# smits-board.net
KiCad netlist of a schematic drawn in EAGLE
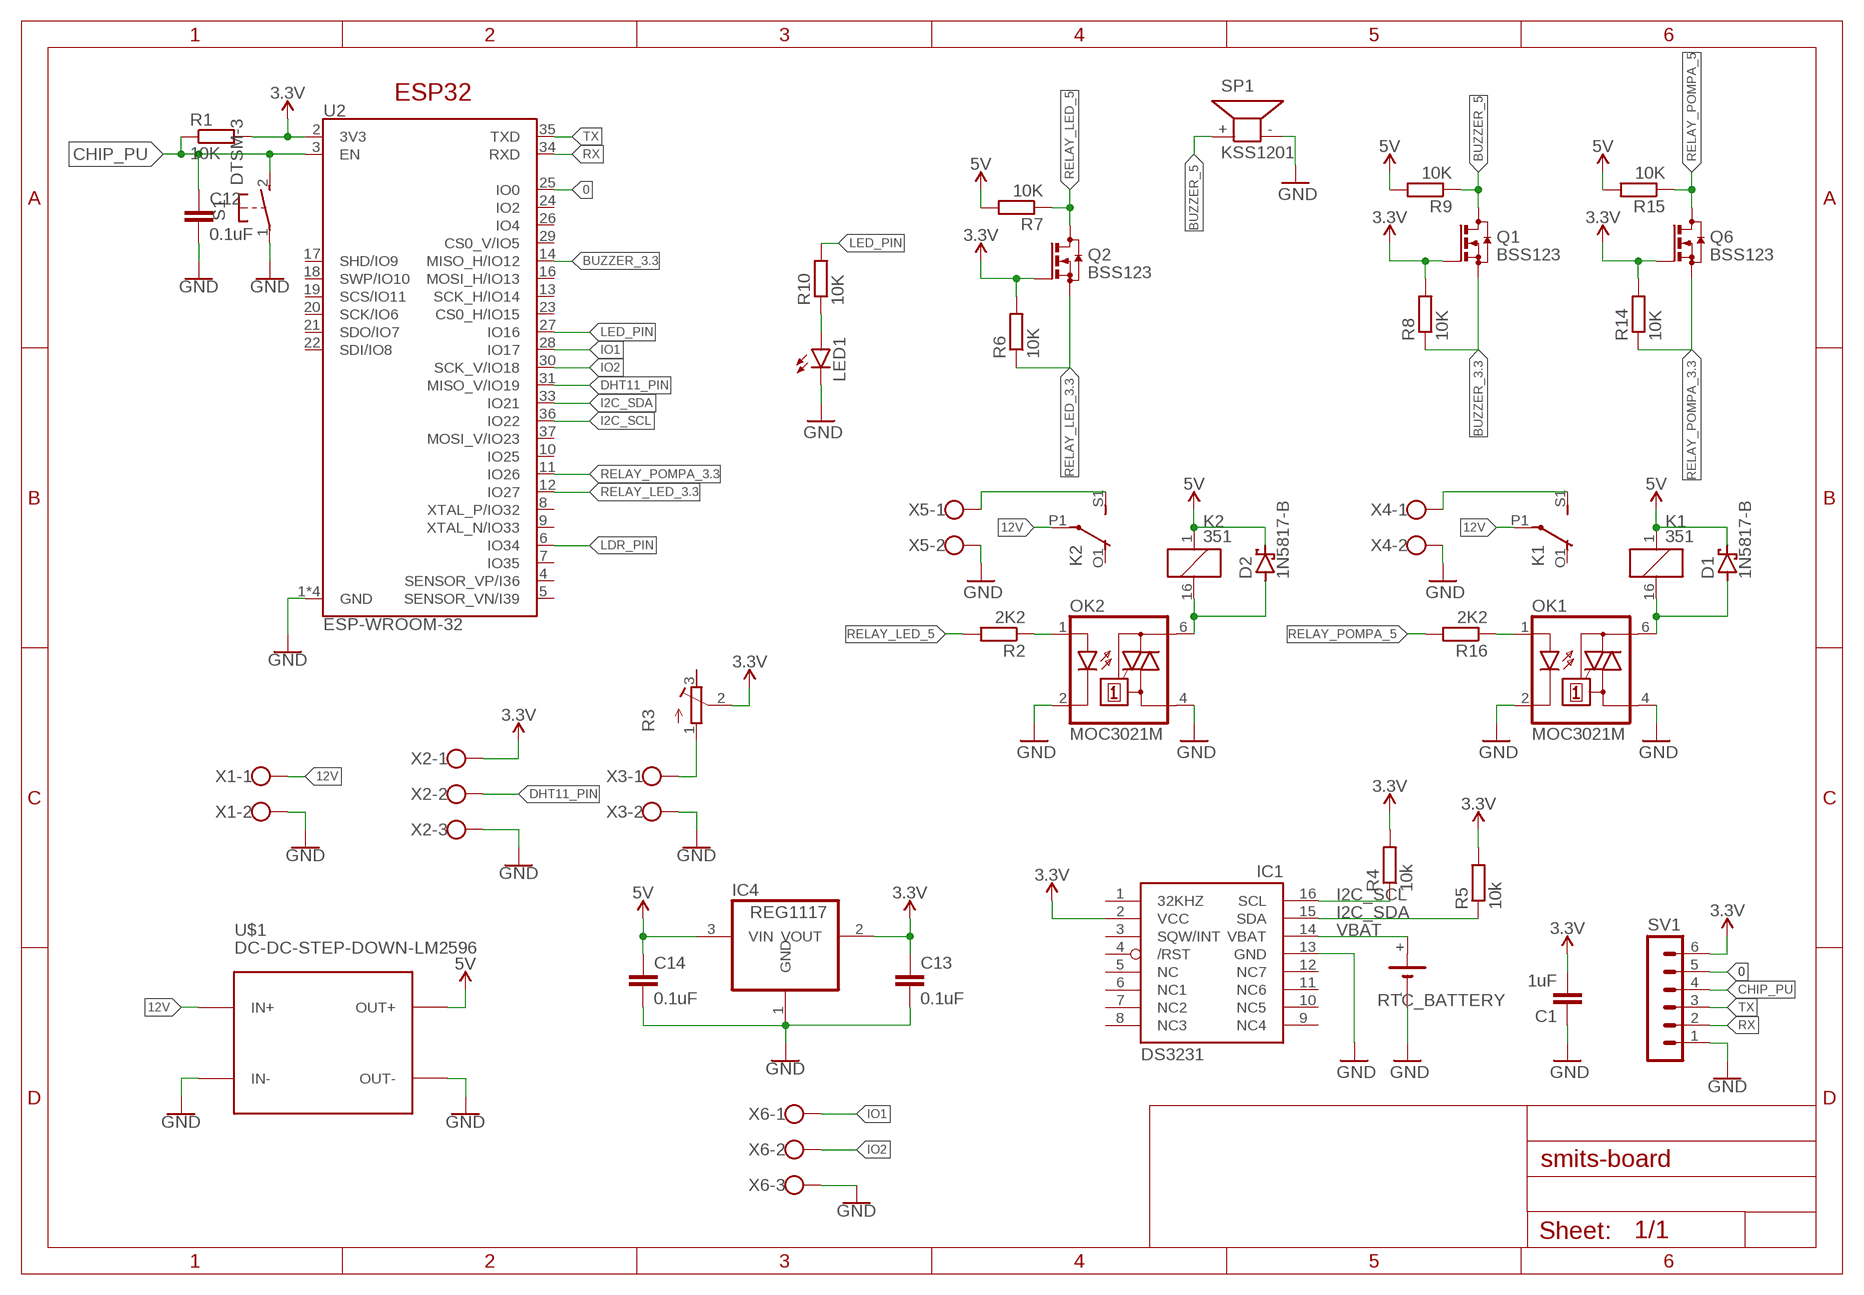
[diagram p0: schematic, sheet 1]

(export (version "E")
  (design (tool "Eeschema 10.0.6"))
  (components
    (comp (ref "C1")
      (value "1uF")
      (footprint "eagle-import:C0805")
      (libsource (lib "eagle-import") (part "C-EUC0805"))
    )
    (comp (ref "C12")
      (value "0.1uF")
      (footprint "eagle-import:C0805")
      (libsource (lib "eagle-import") (part "C-EUC0805"))
    )
    (comp (ref "C13")
      (value "0.1uF")
      (footprint "eagle-import:C0805")
      (libsource (lib "eagle-import") (part "resistor_C-EUC0805"))
    )
    (comp (ref "C14")
      (value "0.1uF")
      (footprint "eagle-import:C0805")
      (libsource (lib "eagle-import") (part "resistor_C-EUC0805"))
    )
    (comp (ref "D1")
      (value "1N5817-B")
      (footprint "eagle-import:DO41-7.6")
      (libsource (lib "eagle-import") (part "1N5817-B"))
    )
    (comp (ref "D2")
      (value "1N5817-B")
      (footprint "eagle-import:DO41-7.6")
      (libsource (lib "eagle-import") (part "1N5817-B"))
    )
    (comp (ref "IC1")
      (value "DS3231/SO")
      (footprint "eagle-import:SO16W")
      (libsource (lib "eagle-import") (part "DS3231/SO"))
    )
    (comp (ref "IC4")
      (value "REG1117")
      (footprint "eagle-import:SOT223")
      (libsource (lib "eagle-import") (part "REG1117"))
    )
    (comp (ref "K1")
      (value "351")
      (footprint "eagle-import:351")
      (libsource (lib "eagle-import") (part "351"))
    )
    (comp (ref "K2")
      (value "351")
      (footprint "eagle-import:351")
      (libsource (lib "eagle-import") (part "351"))
    )
    (comp (ref "LED1")
      (value "LEDCHIP-LED0805")
      (footprint "eagle-import:CHIP-LED0805")
      (libsource (lib "eagle-import") (part "LEDCHIP-LED0805"))
    )
    (comp (ref "OK1")
      (value "MOC3021M")
      (footprint "eagle-import:DIL06")
      (fields (field (name "MF") "FAIRCHILD SEMICONDUCTOR") (field (name "MPN") "MOC3021-M"))
      (libsource (lib "eagle-import") (part "MOC30M21"))
    )
    (comp (ref "OK2")
      (value "MOC3021M")
      (footprint "eagle-import:DIL06")
      (fields (field (name "MF") "FAIRCHILD SEMICONDUCTOR") (field (name "MPN") "MOC3021-M"))
      (libsource (lib "eagle-import") (part "MOC30M21"))
    )
    (comp (ref "Q1")
      (value "BSS123")
      (footprint "eagle-import:SOT23")
      (libsource (lib "eagle-import") (part "BSS123"))
    )
    (comp (ref "Q2")
      (value "BSS123")
      (footprint "eagle-import:SOT23")
      (libsource (lib "eagle-import") (part "BSS123"))
    )
    (comp (ref "Q6")
      (value "BSS123")
      (footprint "eagle-import:SOT23")
      (libsource (lib "eagle-import") (part "BSS123"))
    )
    (comp (ref "R1")
      (value "10K")
      (footprint "eagle-import:R0805")
      (libsource (lib "eagle-import") (part "R-EU_R0805"))
    )
    (comp (ref "R2")
      (value "2K2")
      (footprint "eagle-import:R0805")
      (libsource (lib "eagle-import") (part "resistor_R-EU_R0805"))
    )
    (comp (ref "R3")
      (value "R-TRIMM64W")
      (footprint "eagle-import:RTRIM64W")
      (libsource (lib "eagle-import") (part "R-TRIMM64W"))
    )
    (comp (ref "R4")
      (value "10k")
      (footprint "eagle-import:R0805")
      (libsource (lib "eagle-import") (part "R-EU_R0805"))
    )
    (comp (ref "R5")
      (value "10k")
      (footprint "eagle-import:R0805")
      (libsource (lib "eagle-import") (part "R-EU_R0805"))
    )
    (comp (ref "R6")
      (value "10K")
      (footprint "eagle-import:R0805")
      (libsource (lib "eagle-import") (part "resistor_R-EU_R0805"))
    )
    (comp (ref "R7")
      (value "10K")
      (footprint "eagle-import:R0805")
      (libsource (lib "eagle-import") (part "resistor_R-EU_R0805"))
    )
    (comp (ref "R8")
      (value "10K")
      (footprint "eagle-import:R0805")
      (libsource (lib "eagle-import") (part "resistor_R-EU_R0805"))
    )
    (comp (ref "R9")
      (value "10K")
      (footprint "eagle-import:R0805")
      (libsource (lib "eagle-import") (part "resistor_R-EU_R0805"))
    )
    (comp (ref "R10")
      (value "10K")
      (footprint "eagle-import:R0805")
      (libsource (lib "eagle-import") (part "resistor_R-EU_R0805"))
    )
    (comp (ref "R14")
      (value "10K")
      (footprint "eagle-import:R0805")
      (libsource (lib "eagle-import") (part "resistor_R-EU_R0805"))
    )
    (comp (ref "R15")
      (value "10K")
      (footprint "eagle-import:R0805")
      (libsource (lib "eagle-import") (part "resistor_R-EU_R0805"))
    )
    (comp (ref "R16")
      (value "2K2")
      (footprint "eagle-import:R0805")
      (libsource (lib "eagle-import") (part "resistor_R-EU_R0805"))
    )
    (comp (ref "RTC_BATTERY")
      (value "CH291-1220LF")
      (footprint "eagle-import:CH291-1220LF")
      (libsource (lib "eagle-import") (part "CH291-1220LF"))
    )
    (comp (ref "S1")
      (value "DTSM-3")
      (footprint "eagle-import:DTSM-3")
      (libsource (lib "eagle-import") (part "DTSM-3"))
    )
    (comp (ref "SP1")
      (value "KSS1201")
      (footprint "eagle-import:KSS1201")
      (libsource (lib "eagle-import") (part "KSS1201"))
    )
    (comp (ref "SV1")
      (value "MA06-1")
      (footprint "eagle-import:MA06-1")
      (libsource (lib "eagle-import") (part "MA06-1"))
    )
    (comp (ref "U$1")
      (value "DC-DC-STEP-DOWN-LM2596")
      (footprint "eagle-import:DC-DC-STEP-DOWN-LM2596")
      (libsource (lib "eagle-import") (part "DC-DC-STEP-DOWN-LM2596"))
    )
    (comp (ref "U2")
      (value "ESP-WROOM-32")
      (footprint "eagle-import:ESP-WROOM-32")
      (libsource (lib "eagle-import") (part "ESP-WROOM-32"))
    )
    (comp (ref "X1")
      (value "W237-102")
      (footprint "eagle-import:W237-102")
      (fields (field (name "MPN") "237-102"))
      (libsource (lib "eagle-import") (part "W237-102"))
    )
    (comp (ref "X2")
      (value "W237-103")
      (footprint "eagle-import:W237-103")
      (fields (field (name "MPN") "237-103"))
      (libsource (lib "eagle-import") (part "W237-103"))
    )
    (comp (ref "X3")
      (value "W237-102")
      (footprint "eagle-import:W237-102")
      (fields (field (name "MPN") "237-102"))
      (libsource (lib "eagle-import") (part "W237-102"))
    )
    (comp (ref "X4")
      (value "W237-102")
      (footprint "eagle-import:W237-102")
      (fields (field (name "MPN") "237-102"))
      (libsource (lib "eagle-import") (part "W237-102"))
    )
    (comp (ref "X5")
      (value "W237-102")
      (footprint "eagle-import:W237-102")
      (fields (field (name "MPN") "237-102"))
      (libsource (lib "eagle-import") (part "W237-102"))
    )
    (comp (ref "X6")
      (value "W237-103")
      (footprint "eagle-import:W237-103")
      (fields (field (name "MPN") "237-103"))
      (libsource (lib "eagle-import") (part "W237-103"))
    )
  )
  (nets
    (net (code "1") (name "/VBAT") (class "Default")
      (node (ref "IC1") (pin "14") (pinfunction "VBAT_14") (pintype "power_in"))
      (node (ref "RTC_BATTERY") (pin "+") (pinfunction "+_+") (pintype "passive"))
    )
    (net (code "2") (name "0") (class "Default")
      (node (ref "SV1") (pin "5") (pinfunction "5_5") (pintype "passive"))
      (node (ref "U2") (pin "25") (pinfunction "IO0_25") (pintype "bidirectional"))
    )
    (net (code "3") (name "3.3V") (class "Default")
      (node (ref "C1") (pin "2") (pinfunction "2_2") (pintype "passive"))
      (node (ref "C13") (pin "1") (pinfunction "1_1") (pintype "passive"))
      (node (ref "IC1") (pin "2") (pinfunction "VCC_2") (pintype "power_in"))
      (node (ref "IC4") (pin "2") (pinfunction "VOUT_2") (pintype "output"))
      (node (ref "Q1") (pin "1") (pinfunction "G_1") (pintype "passive"))
      (node (ref "Q2") (pin "1") (pinfunction "G_1") (pintype "passive"))
      (node (ref "Q6") (pin "1") (pinfunction "G_1") (pintype "passive"))
      (node (ref "R1") (pin "2") (pinfunction "2_2") (pintype "passive"))
      (node (ref "R14") (pin "2") (pinfunction "2_2") (pintype "passive"))
      (node (ref "R3") (pin "2") (pinfunction "S_2") (pintype "passive"))
      (node (ref "R4") (pin "2") (pinfunction "2_2") (pintype "passive"))
      (node (ref "R5") (pin "2") (pinfunction "2_2") (pintype "passive"))
      (node (ref "R6") (pin "2") (pinfunction "2_2") (pintype "passive"))
      (node (ref "R8") (pin "2") (pinfunction "2_2") (pintype "passive"))
      (node (ref "SV1") (pin "6") (pinfunction "6_6") (pintype "passive"))
      (node (ref "U2") (pin "2") (pinfunction "3V3_2") (pintype "bidirectional"))
      (node (ref "X2") (pin "1") (pinfunction "KL_1") (pintype "passive"))
    )
    (net (code "4") (name "5V") (class "Default")
      (node (ref "C14") (pin "1") (pinfunction "1_1") (pintype "passive"))
      (node (ref "D1") (pin "C") (pinfunction "C_C") (pintype "passive"))
      (node (ref "D2") (pin "C") (pinfunction "C_C") (pintype "passive"))
      (node (ref "IC4") (pin "3") (pinfunction "VIN_3") (pintype "input"))
      (node (ref "K1") (pin "1") (pinfunction "1_1") (pintype "passive"))
      (node (ref "K2") (pin "1") (pinfunction "1_1") (pintype "passive"))
      (node (ref "R15") (pin "2") (pinfunction "2_2") (pintype "passive"))
      (node (ref "R7") (pin "2") (pinfunction "2_2") (pintype "passive"))
      (node (ref "R9") (pin "2") (pinfunction "2_2") (pintype "passive"))
      (node (ref "U$1") (pin "OUT+") (pinfunction "OUT+_OUT+") (pintype "bidirectional"))
    )
    (net (code "5") (name "12V") (class "Default")
      (node (ref "K1") (pin "P1") (pinfunction "P_P1") (pintype "passive"))
      (node (ref "K2") (pin "P1") (pinfunction "P_P1") (pintype "passive"))
      (node (ref "U$1") (pin "IN+") (pinfunction "IN+_IN+") (pintype "bidirectional"))
      (node (ref "X1") (pin "1") (pinfunction "KL_1") (pintype "passive"))
    )
    (net (code "6") (name "BUZZER_3.3") (class "Default")
      (node (ref "Q1") (pin "2") (pinfunction "S_2") (pintype "passive"))
      (node (ref "R8") (pin "1") (pinfunction "1_1") (pintype "passive"))
      (node (ref "U2") (pin "14") (pinfunction "MISO_H/IO12_14") (pintype "bidirectional"))
    )
    (net (code "7") (name "BUZZER_5") (class "Default")
      (node (ref "Q1") (pin "3") (pinfunction "D_3") (pintype "passive"))
      (node (ref "R9") (pin "1") (pinfunction "1_1") (pintype "passive"))
      (node (ref "SP1") (pin "+") (pinfunction "1_+") (pintype "passive"))
    )
    (net (code "8") (name "CHIP_PU") (class "Default")
      (node (ref "C12") (pin "1") (pinfunction "1_1") (pintype "passive"))
      (node (ref "R1") (pin "1") (pinfunction "1_1") (pintype "passive"))
      (node (ref "S1") (pin "2") (pinfunction "2_2") (pintype "passive"))
      (node (ref "SV1") (pin "4") (pinfunction "4_4") (pintype "passive"))
      (node (ref "U2") (pin "3") (pinfunction "EN_3") (pintype "bidirectional"))
    )
    (net (code "9") (name "DHT11_PIN") (class "Default")
      (node (ref "U2") (pin "31") (pinfunction "MISO_V/IO19_31") (pintype "bidirectional"))
      (node (ref "X2") (pin "2") (pinfunction "KL_2") (pintype "passive"))
    )
    (net (code "10") (name "GND") (class "Default")
      (node (ref "C1") (pin "1") (pinfunction "1_1") (pintype "passive"))
      (node (ref "C12") (pin "2") (pinfunction "2_2") (pintype "passive"))
      (node (ref "C13") (pin "2") (pinfunction "2_2") (pintype "passive"))
      (node (ref "C14") (pin "2") (pinfunction "2_2") (pintype "passive"))
      (node (ref "IC1") (pin "13") (pinfunction "GND_13") (pintype "power_in"))
      (node (ref "IC4") (pin "1") (pinfunction "GND_1") (pintype "power_in"))
      (node (ref "LED1") (pin "C") (pinfunction "C_C") (pintype "passive"))
      (node (ref "OK1") (pin "2") (pinfunction "C_2") (pintype "passive"))
      (node (ref "OK1") (pin "4") (pinfunction "A1_4") (pintype "passive"))
      (node (ref "OK2") (pin "2") (pinfunction "C_2") (pintype "passive"))
      (node (ref "OK2") (pin "4") (pinfunction "A1_4") (pintype "passive"))
      (node (ref "RTC_BATTERY") (pin "-") (pinfunction "-_-") (pintype "passive"))
      (node (ref "S1") (pin "1") (pinfunction "1_1") (pintype "passive"))
      (node (ref "SP1") (pin "-") (pinfunction "2_-") (pintype "passive"))
      (node (ref "SV1") (pin "1") (pinfunction "1_1") (pintype "passive"))
      (node (ref "U$1") (pin "IN-") (pinfunction "IN-_IN-") (pintype "bidirectional"))
      (node (ref "U$1") (pin "OUT-") (pinfunction "OUT-_OUT-") (pintype "bidirectional"))
      (node (ref "U2") (pin "1") (pinfunction "GND_1") (pintype "bidirectional"))
      (node (ref "U2") (pin "15") (pinfunction "GND_15") (pintype "bidirectional"))
      (node (ref "U2") (pin "38") (pinfunction "GND_38") (pintype "bidirectional"))
      (node (ref "U2") (pin "GND") (pinfunction "GND_GND") (pintype "bidirectional"))
      (node (ref "X1") (pin "2") (pinfunction "KL_2") (pintype "passive"))
      (node (ref "X2") (pin "3") (pinfunction "KL_3") (pintype "passive"))
      (node (ref "X3") (pin "2") (pinfunction "KL_2") (pintype "passive"))
      (node (ref "X4") (pin "2") (pinfunction "KL_2") (pintype "passive"))
      (node (ref "X5") (pin "2") (pinfunction "KL_2") (pintype "passive"))
      (node (ref "X6") (pin "3") (pinfunction "KL_3") (pintype "passive"))
    )
    (net (code "11") (name "I2C_SCL") (class "Default")
      (node (ref "IC1") (pin "16") (pinfunction "SCL_16") (pintype "bidirectional"))
      (node (ref "R4") (pin "1") (pinfunction "1_1") (pintype "passive"))
      (node (ref "U2") (pin "36") (pinfunction "IO22_36") (pintype "bidirectional"))
    )
    (net (code "12") (name "I2C_SDA") (class "Default")
      (node (ref "IC1") (pin "15") (pinfunction "SDA_15") (pintype "bidirectional"))
      (node (ref "R5") (pin "1") (pinfunction "1_1") (pintype "passive"))
      (node (ref "U2") (pin "33") (pinfunction "IO21_33") (pintype "bidirectional"))
    )
    (net (code "13") (name "IO1") (class "Default")
      (node (ref "U2") (pin "28") (pinfunction "IO17_28") (pintype "bidirectional"))
      (node (ref "X6") (pin "1") (pinfunction "KL_1") (pintype "passive"))
    )
    (net (code "14") (name "IO2") (class "Default")
      (node (ref "U2") (pin "30") (pinfunction "SCK_V/IO18_30") (pintype "bidirectional"))
      (node (ref "X6") (pin "2") (pinfunction "KL_2") (pintype "passive"))
    )
    (net (code "15") (name "LDR_PIN") (class "Default")
      (node (ref "U2") (pin "6") (pinfunction "IO34_6") (pintype "bidirectional"))
    )
    (net (code "16") (name "LED_PIN") (class "Default")
      (node (ref "R10") (pin "2") (pinfunction "2_2") (pintype "passive"))
      (node (ref "U2") (pin "27") (pinfunction "IO16_27") (pintype "bidirectional"))
    )
    (net (code "17") (name "Net-(K1A-2)") (class "Default")
      (node (ref "D1") (pin "A") (pinfunction "A_A") (pintype "passive"))
      (node (ref "K1") (pin "16") (pinfunction "2_16") (pintype "passive"))
      (node (ref "OK1") (pin "6") (pinfunction "A2_6") (pintype "passive"))
    )
    (net (code "18") (name "Net-(K1B-S)") (class "Default")
      (node (ref "K1") (pin "S1") (pinfunction "S_S1") (pintype "passive"))
      (node (ref "X4") (pin "1") (pinfunction "KL_1") (pintype "passive"))
    )
    (net (code "19") (name "Net-(K2A-2)") (class "Default")
      (node (ref "D2") (pin "A") (pinfunction "A_A") (pintype "passive"))
      (node (ref "K2") (pin "16") (pinfunction "2_16") (pintype "passive"))
      (node (ref "OK2") (pin "6") (pinfunction "A2_6") (pintype "passive"))
    )
    (net (code "20") (name "Net-(K2B-S)") (class "Default")
      (node (ref "K2") (pin "S1") (pinfunction "S_S1") (pintype "passive"))
      (node (ref "X5") (pin "1") (pinfunction "KL_1") (pintype "passive"))
    )
    (net (code "21") (name "Net-(LED1-PadA)") (class "Default")
      (node (ref "LED1") (pin "A") (pinfunction "A_A") (pintype "passive"))
      (node (ref "R10") (pin "1") (pinfunction "1_1") (pintype "passive"))
    )
    (net (code "22") (name "Net-(OK1-A)") (class "Default")
      (node (ref "OK1") (pin "1") (pinfunction "A_1") (pintype "passive"))
      (node (ref "R16") (pin "1") (pinfunction "1_1") (pintype "passive"))
    )
    (net (code "23") (name "Net-(OK2-A)") (class "Default")
      (node (ref "OK2") (pin "1") (pinfunction "A_1") (pintype "passive"))
      (node (ref "R2") (pin "1") (pinfunction "1_1") (pintype "passive"))
    )
    (net (code "24") (name "Net-(R3-A)") (class "Default")
      (node (ref "R3") (pin "1") (pinfunction "A_1") (pintype "passive"))
      (node (ref "X3") (pin "1") (pinfunction "KL_1") (pintype "passive"))
    )
    (net (code "25") (name "RELAY_LED_3.3") (class "Default")
      (node (ref "Q2") (pin "2") (pinfunction "S_2") (pintype "passive"))
      (node (ref "R6") (pin "1") (pinfunction "1_1") (pintype "passive"))
      (node (ref "U2") (pin "12") (pinfunction "IO27_12") (pintype "bidirectional"))
    )
    (net (code "26") (name "RELAY_LED_5") (class "Default")
      (node (ref "Q2") (pin "3") (pinfunction "D_3") (pintype "passive"))
      (node (ref "R2") (pin "2") (pinfunction "2_2") (pintype "passive"))
      (node (ref "R7") (pin "1") (pinfunction "1_1") (pintype "passive"))
    )
    (net (code "27") (name "RELAY_POMPA_3.3") (class "Default")
      (node (ref "Q6") (pin "2") (pinfunction "S_2") (pintype "passive"))
      (node (ref "R14") (pin "1") (pinfunction "1_1") (pintype "passive"))
      (node (ref "U2") (pin "11") (pinfunction "IO26_11") (pintype "bidirectional"))
    )
    (net (code "28") (name "RELAY_POMPA_5") (class "Default")
      (node (ref "Q6") (pin "3") (pinfunction "D_3") (pintype "passive"))
      (node (ref "R15") (pin "1") (pinfunction "1_1") (pintype "passive"))
      (node (ref "R16") (pin "2") (pinfunction "2_2") (pintype "passive"))
    )
    (net (code "29") (name "RX") (class "Default")
      (node (ref "SV1") (pin "2") (pinfunction "2_2") (pintype "passive"))
      (node (ref "U2") (pin "34") (pinfunction "RXD_34") (pintype "bidirectional"))
    )
    (net (code "30") (name "TX") (class "Default")
      (node (ref "SV1") (pin "3") (pinfunction "3_3") (pintype "passive"))
      (node (ref "U2") (pin "35") (pinfunction "TXD_35") (pintype "bidirectional"))
    )
    (net (code "31") (name "unconnected-(IC1-32KHZ-Pad1)") (class "Default")
      (node (ref "IC1") (pin "1") (pinfunction "32KHZ_1") (pintype "output"))
    )
    (net (code "32") (name "unconnected-(IC1-NC-Pad5)") (class "Default")
      (node (ref "IC1") (pin "5") (pinfunction "NC_5") (pintype "no_connect"))
    )
    (net (code "33") (name "unconnected-(IC1-NC1-Pad6)") (class "Default")
      (node (ref "IC1") (pin "6") (pinfunction "NC1_6") (pintype "no_connect"))
    )
    (net (code "34") (name "unconnected-(IC1-NC2-Pad7)") (class "Default")
      (node (ref "IC1") (pin "7") (pinfunction "NC2_7") (pintype "no_connect"))
    )
    (net (code "35") (name "unconnected-(IC1-NC3-Pad8)") (class "Default")
      (node (ref "IC1") (pin "8") (pinfunction "NC3_8") (pintype "no_connect"))
    )
    (net (code "36") (name "unconnected-(IC1-NC4-Pad9)") (class "Default")
      (node (ref "IC1") (pin "9") (pinfunction "NC4_9") (pintype "no_connect"))
    )
    (net (code "37") (name "unconnected-(IC1-NC5-Pad10)") (class "Default")
      (node (ref "IC1") (pin "10") (pinfunction "NC5_10") (pintype "no_connect"))
    )
    (net (code "38") (name "unconnected-(IC1-NC6-Pad11)") (class "Default")
      (node (ref "IC1") (pin "11") (pinfunction "NC6_11") (pintype "no_connect"))
    )
    (net (code "39") (name "unconnected-(IC1-NC7-Pad12)") (class "Default")
      (node (ref "IC1") (pin "12") (pinfunction "NC7_12") (pintype "no_connect"))
    )
    (net (code "40") (name "unconnected-(IC1-SQW{slash}INT-Pad3)") (class "Default")
      (node (ref "IC1") (pin "3") (pinfunction "SQW/INT_3") (pintype "output"))
    )
    (net (code "41") (name "unconnected-(IC1-{slash}RST-Pad4)") (class "Default")
      (node (ref "IC1") (pin "4") (pinfunction "/RST_4") (pintype "passive"))
    )
    (net (code "42") (name "unconnected-(K1B-O-PadO1)") (class "Default")
      (node (ref "K1") (pin "O1") (pinfunction "O_O1") (pintype "passive"))
    )
    (net (code "43") (name "unconnected-(K2B-O-PadO1)") (class "Default")
      (node (ref "K2") (pin "O1") (pinfunction "O_O1") (pintype "passive"))
    )
    (net (code "44") (name "unconnected-(R3-E-Pad3)") (class "Default")
      (node (ref "R3") (pin "3") (pinfunction "E_3") (pintype "passive"))
    )
    (net (code "45") (name "unconnected-(U2-CS0_H{slash}IO15-Pad23)") (class "Default")
      (node (ref "U2") (pin "23") (pinfunction "CS0_H/IO15_23") (pintype "bidirectional"))
    )
    (net (code "46") (name "unconnected-(U2-CS0_V{slash}IO5-Pad29)") (class "Default")
      (node (ref "U2") (pin "29") (pinfunction "CS0_V/IO5_29") (pintype "bidirectional"))
    )
    (net (code "47") (name "unconnected-(U2-IO2-Pad24)") (class "Default")
      (node (ref "U2") (pin "24") (pinfunction "IO2_24") (pintype "bidirectional"))
    )
    (net (code "48") (name "unconnected-(U2-IO4-Pad26)") (class "Default")
      (node (ref "U2") (pin "26") (pinfunction "IO4_26") (pintype "bidirectional"))
    )
    (net (code "49") (name "unconnected-(U2-IO25-Pad10)") (class "Default")
      (node (ref "U2") (pin "10") (pinfunction "IO25_10") (pintype "bidirectional"))
    )
    (net (code "50") (name "unconnected-(U2-IO35-Pad7)") (class "Default")
      (node (ref "U2") (pin "7") (pinfunction "IO35_7") (pintype "bidirectional"))
    )
    (net (code "51") (name "unconnected-(U2-MOSI_H{slash}IO13-Pad16)") (class "Default")
      (node (ref "U2") (pin "16") (pinfunction "MOSI_H/IO13_16") (pintype "bidirectional"))
    )
    (net (code "52") (name "unconnected-(U2-MOSI_V{slash}IO23-Pad37)") (class "Default")
      (node (ref "U2") (pin "37") (pinfunction "MOSI_V/IO23_37") (pintype "bidirectional"))
    )
    (net (code "53") (name "unconnected-(U2-SCK_H{slash}IO14-Pad13)") (class "Default")
      (node (ref "U2") (pin "13") (pinfunction "SCK_H/IO14_13") (pintype "bidirectional"))
    )
    (net (code "54") (name "unconnected-(U2-SCK{slash}IO6-Pad20)") (class "Default")
      (node (ref "U2") (pin "20") (pinfunction "SCK/IO6_20") (pintype "bidirectional"))
    )
    (net (code "55") (name "unconnected-(U2-SCS{slash}IO11-Pad19)") (class "Default")
      (node (ref "U2") (pin "19") (pinfunction "SCS/IO11_19") (pintype "bidirectional"))
    )
    (net (code "56") (name "unconnected-(U2-SDI{slash}IO8-Pad22)") (class "Default")
      (node (ref "U2") (pin "22") (pinfunction "SDI/IO8_22") (pintype "bidirectional"))
    )
    (net (code "57") (name "unconnected-(U2-SDO{slash}IO7-Pad21)") (class "Default")
      (node (ref "U2") (pin "21") (pinfunction "SDO/IO7_21") (pintype "bidirectional"))
    )
    (net (code "58") (name "unconnected-(U2-SENSOR_VN{slash}I39-Pad5)") (class "Default")
      (node (ref "U2") (pin "5") (pinfunction "SENSOR_VN/I39_5") (pintype "bidirectional"))
    )
    (net (code "59") (name "unconnected-(U2-SENSOR_VP{slash}I36-Pad4)") (class "Default")
      (node (ref "U2") (pin "4") (pinfunction "SENSOR_VP/I36_4") (pintype "bidirectional"))
    )
    (net (code "60") (name "unconnected-(U2-SHD{slash}IO9-Pad17)") (class "Default")
      (node (ref "U2") (pin "17") (pinfunction "SHD/IO9_17") (pintype "bidirectional"))
    )
    (net (code "61") (name "unconnected-(U2-SWP{slash}IO10-Pad18)") (class "Default")
      (node (ref "U2") (pin "18") (pinfunction "SWP/IO10_18") (pintype "bidirectional"))
    )
    (net (code "62") (name "unconnected-(U2-XTAL_N{slash}IO33-Pad9)") (class "Default")
      (node (ref "U2") (pin "9") (pinfunction "XTAL_N/IO33_9") (pintype "bidirectional"))
    )
    (net (code "63") (name "unconnected-(U2-XTAL_P{slash}IO32-Pad8)") (class "Default")
      (node (ref "U2") (pin "8") (pinfunction "XTAL_P/IO32_8") (pintype "bidirectional"))
    )
  )
)
